# VEML7700-Breakout_v10.net
KiCad netlist of a schematic drawn in EAGLE
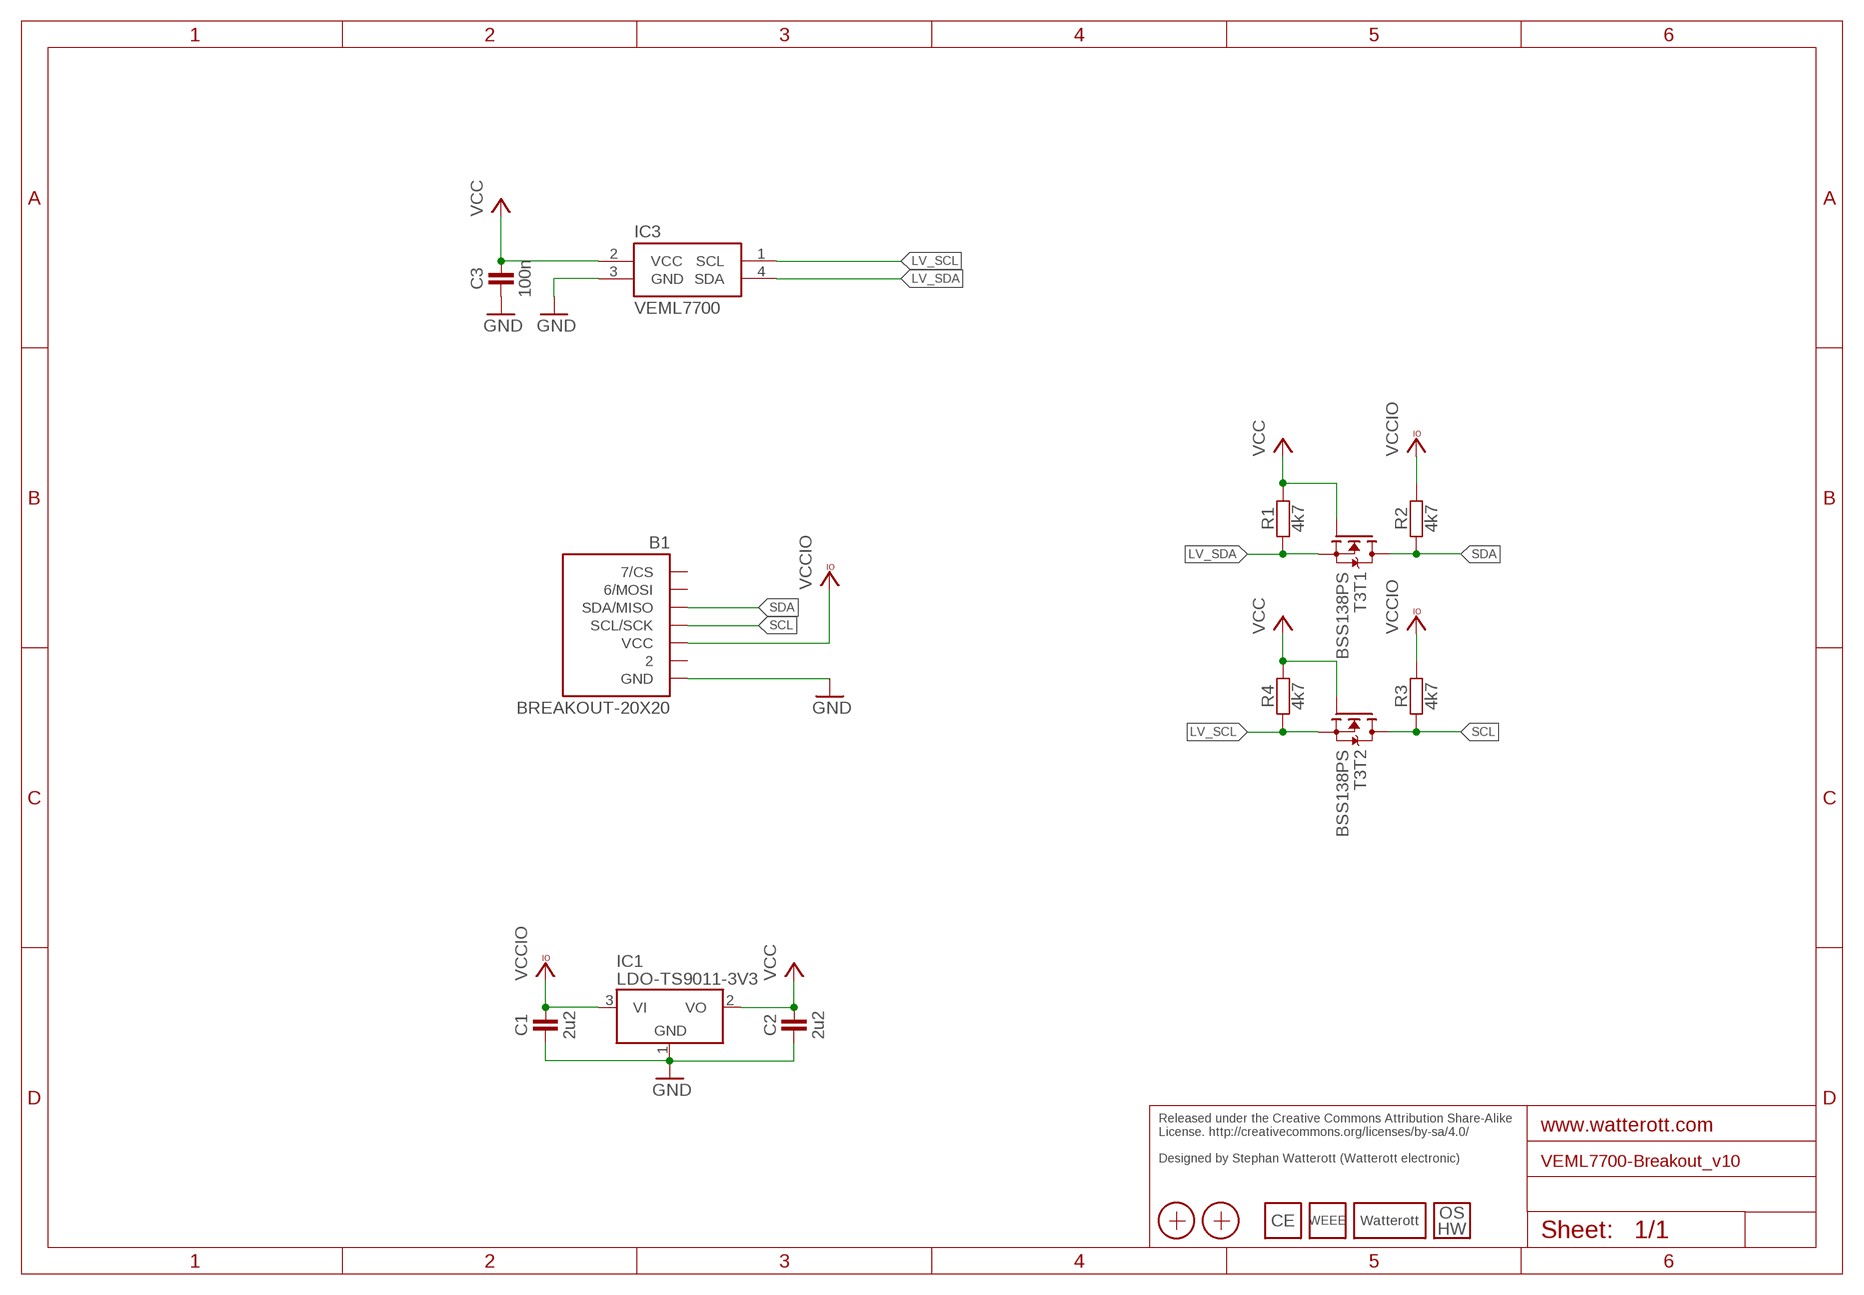
[diagram p0: schematic, sheet 1]

(export (version "E")
  (design (tool "Eeschema 10.0.6"))
  (components
    (comp (ref "B1")
      (value "BREAKOUT-20X20")
      (footprint "eagle-import:BREAKOUT-20X20")
      (libsource (lib "eagle-import") (part "BREAKOUT-20X20"))
    )
    (comp (ref "C1")
      (value "2u2")
      (footprint "eagle-import:C0402")
      (libsource (lib "eagle-import") (part "CAPACITOR-0402"))
    )
    (comp (ref "C2")
      (value "2u2")
      (footprint "eagle-import:C0402")
      (libsource (lib "eagle-import") (part "CAPACITOR-0402"))
    )
    (comp (ref "C3")
      (value "100n")
      (footprint "eagle-import:C0402")
      (libsource (lib "eagle-import") (part "CAPACITOR-0402"))
    )
    (comp (ref "IC1")
      (value "LDO-TS9011-3V3")
      (footprint "eagle-import:SOT23")
      (libsource (lib "eagle-import") (part "LDO-TS9011-3V3"))
    )
    (comp (ref "IC3")
      (value "VEML7700")
      (footprint "eagle-import:VEML7700")
      (libsource (lib "eagle-import") (part "VEML7700"))
    )
    (comp (ref "LOGO3")
      (value "LOGO_WEEE-4")
      (footprint "eagle-import:WEEE_4MM")
      (libsource (lib "eagle-import") (part "LOGO_WEEE-4"))
    )
    (comp (ref "LOGO4")
      (value "LOGO_CE-4")
      (footprint "eagle-import:CE_4MM")
      (libsource (lib "eagle-import") (part "LOGO_CE-4"))
    )
    (comp (ref "LOGO5")
      (value "LOGO_SPARK-4")
      (footprint "eagle-import:SPARK_4MM")
      (libsource (lib "eagle-import") (part "LOGO_SPARK-4"))
    )
    (comp (ref "LOGO6")
      (value "LOGO_OSHW-2")
      (footprint "eagle-import:OSHW_2MM")
      (libsource (lib "eagle-import") (part "LOGO_OSHW-2"))
    )
    (comp (ref "R1")
      (value "4k7")
      (footprint "eagle-import:C0402")
      (libsource (lib "eagle-import") (part "RESISTOR-0402"))
    )
    (comp (ref "R2")
      (value "4k7")
      (footprint "eagle-import:C0402")
      (libsource (lib "eagle-import") (part "RESISTOR-0402"))
    )
    (comp (ref "R3")
      (value "4k7")
      (footprint "eagle-import:C0402")
      (libsource (lib "eagle-import") (part "RESISTOR-0402"))
    )
    (comp (ref "R4")
      (value "4k7")
      (footprint "eagle-import:C0402")
      (libsource (lib "eagle-import") (part "RESISTOR-0402"))
    )
    (comp (ref "T3")
      (value "BSS138PS")
      (footprint "eagle-import:SOT363")
      (libsource (lib "eagle-import") (part "BSS138PS"))
    )
    (comp (ref "X1")
      (value "PASSER-07")
      (footprint "eagle-import:PASSER_07MM")
      (libsource (lib "eagle-import") (part "PASSER-07"))
    )
    (comp (ref "X2")
      (value "PASSER-07")
      (footprint "eagle-import:PASSER_07MM")
      (libsource (lib "eagle-import") (part "PASSER-07"))
    )
  )
  (nets
    (net (code "1") (name "GND") (class "Default")
      (node (ref "B1") (pin "GND") (pinfunction "GND_GND") (pintype "power_in"))
      (node (ref "C1") (pin "1") (pinfunction "1_1") (pintype "passive"))
      (node (ref "C2") (pin "1") (pinfunction "1_1") (pintype "passive"))
      (node (ref "C3") (pin "1") (pinfunction "1_1") (pintype "passive"))
      (node (ref "IC1") (pin "1") (pinfunction "GND_1") (pintype "passive"))
      (node (ref "IC3") (pin "3") (pinfunction "GND_3") (pintype "power_in"))
    )
    (net (code "2") (name "LV_SCL") (class "Default")
      (node (ref "IC3") (pin "1") (pinfunction "SCL_1") (pintype "bidirectional"))
      (node (ref "R4") (pin "1") (pinfunction "1_1") (pintype "passive"))
      (node (ref "T3") (pin "4") (pinfunction "S_4") (pintype "passive"))
    )
    (net (code "3") (name "LV_SDA") (class "Default")
      (node (ref "IC3") (pin "4") (pinfunction "SDA_4") (pintype "bidirectional"))
      (node (ref "R1") (pin "1") (pinfunction "1_1") (pintype "passive"))
      (node (ref "T3") (pin "1") (pinfunction "S_1") (pintype "passive"))
    )
    (net (code "4") (name "SCL") (class "Default")
      (node (ref "B1") (pin "SCL/SCK") (pinfunction "SCL/SCK_SCL/SCK") (pintype "bidirectional"))
      (node (ref "R3") (pin "1") (pinfunction "1_1") (pintype "passive"))
      (node (ref "T3") (pin "3") (pinfunction "D_3") (pintype "passive"))
    )
    (net (code "5") (name "SDA") (class "Default")
      (node (ref "B1") (pin "SDA/MISO") (pinfunction "SDA/MISO_SDA/MISO") (pintype "bidirectional"))
      (node (ref "R2") (pin "1") (pinfunction "1_1") (pintype "passive"))
      (node (ref "T3") (pin "6") (pinfunction "D_6") (pintype "passive"))
    )
    (net (code "6") (name "VCC") (class "Default")
      (node (ref "C2") (pin "2") (pinfunction "2_2") (pintype "passive"))
      (node (ref "C3") (pin "2") (pinfunction "2_2") (pintype "passive"))
      (node (ref "IC1") (pin "2") (pinfunction "VO_2") (pintype "passive"))
      (node (ref "IC3") (pin "2") (pinfunction "VCC_2") (pintype "power_in"))
      (node (ref "R1") (pin "2") (pinfunction "2_2") (pintype "passive"))
      (node (ref "R4") (pin "2") (pinfunction "2_2") (pintype "passive"))
      (node (ref "T3") (pin "2") (pinfunction "G_2") (pintype "passive"))
      (node (ref "T3") (pin "5") (pinfunction "G_5") (pintype "passive"))
    )
    (net (code "7") (name "VCCIO") (class "Default")
      (node (ref "B1") (pin "VCC") (pinfunction "VCC_VCC") (pintype "power_in"))
      (node (ref "C1") (pin "2") (pinfunction "2_2") (pintype "passive"))
      (node (ref "IC1") (pin "3") (pinfunction "VI_3") (pintype "input"))
      (node (ref "R2") (pin "2") (pinfunction "2_2") (pintype "passive"))
      (node (ref "R3") (pin "2") (pinfunction "2_2") (pintype "passive"))
    )
    (net (code "8") (name "unconnected-(B1-6{slash}MOSI-PadMOSI)") (class "Default")
      (node (ref "B1") (pin "MOSI") (pinfunction "6/MOSI_MOSI") (pintype "bidirectional"))
    )
    (net (code "9") (name "unconnected-(B1-7{slash}CS-PadCS)") (class "Default")
      (node (ref "B1") (pin "CS") (pinfunction "7/CS_CS") (pintype "bidirectional"))
    )
    (net (code "10") (name "unconnected-(B1-Pad2)") (class "Default")
      (node (ref "B1") (pin "2") (pinfunction "2_2") (pintype "bidirectional"))
    )
  )
)
